# Power.net
KiCad netlist of a schematic drawn in Altium Designer
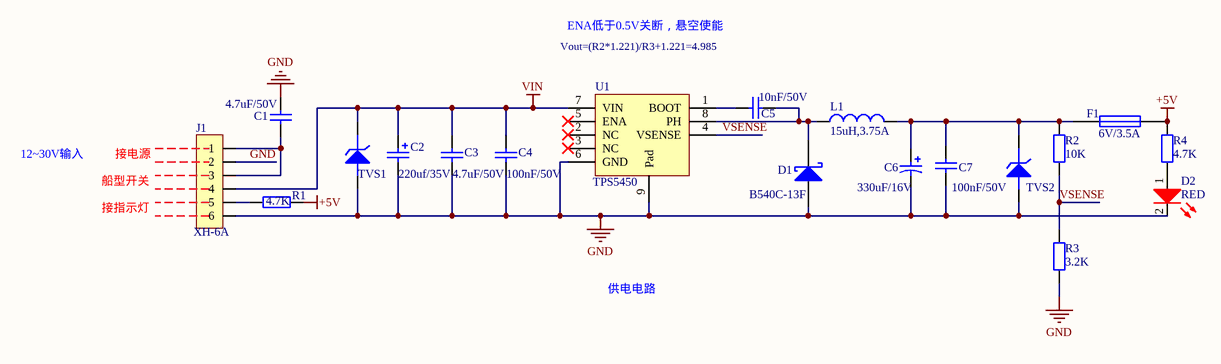
[diagram p0: Power.SchDoc]

(export (version "E")
  (design (tool "Eeschema 10.0.6"))
  (components
    (comp (ref "C1")
      (value "4.7uF/50V")
      (footprint "0603C")
      (description "瓷片电容,4.7uF,5%,X7R,50V,0603")
      (libsource (lib "SR SCH Library V02") (part "C4.7uF-0603"))
    )
    (comp (ref "C2")
      (value "220uf/35V")
      (footprint "CES-8x10R5mm")
      (description "铝电解电容,220uF,20%,35V,8*11.5")
      (libsource (lib "SR SCH Library V02") (part "C220uf/35V-8*11.5"))
    )
    (comp (ref "C3")
      (value "4.7uF/50V")
      (footprint "0603C")
      (description "瓷片电容,4.7uF,5%,X7R,50V,0603")
      (libsource (lib "SR SCH Library V02") (part "C4.7uF-0603"))
    )
    (comp (ref "C4")
      (value "100nF/50V")
      (footprint "0603C")
      (description "瓷片电容,100nF,5%,X7R,50V,0603")
      (libsource (lib "SR SCH Library V02") (part "C100nF/50V-0603"))
    )
    (comp (ref "C5")
      (value "10nF/50V")
      (footprint "0603C")
      (description "瓷片电容,10nF,5%,X7R,50V,0603")
      (libsource (lib "SR SCH Library V02") (part "C10nF/50V-0603"))
    )
    (comp (ref "C6")
      (value "330uF/16V")
      (footprint "CES-8 X11R7MM")
      (description "铝电解电容，330uF/16V，8*11.7")
      (libsource (lib "SR SCH Library V02") (part "C330uF/16V-8*11.7"))
    )
    (comp (ref "C7")
      (value "100nF/50V")
      (footprint "0603C")
      (description "瓷片电容,100nF,5%,X7R,50V,0603")
      (libsource (lib "SR SCH Library V02") (part "C100nF/50V-0603"))
    )
    (comp (ref "D1")
      (value "B540C-13F")
      (footprint "SMC")
      (description "肖特基二极管, 40V/5A, SMC（DO-214AB）封装")
      (libsource (lib "SR SCH Library V02") (part "B540C-13-F"))
    )
    (comp (ref "D2")
      (value "RED")
      (footprint "0603D")
      (description "LED，红光，0603")
      (libsource (lib "SR SCH Library V02") (part "LED-RED-0603"))
    )
    (comp (ref "F1")
      (value "6V/3.5A")
      (footprint "F1812")
      (description "保险丝,6V,3.5A,慢断,1812封装")
      (libsource (lib "SR SCH Library V02") (part "F-6V/3.5A"))
    )
    (comp (ref "J1")
      (value "XH-6A")
      (footprint "CN6-2.54")
      (description "CONN,XH-6A,6PIN,2.54mm插座")
      (libsource (lib "SR SCH Library V02") (part "CONN-XH-6A"))
    )
    (comp (ref "L1")
      (value "15uH,3.75A")
      (footprint "L12*12*6")
      (description "744771115，15uH，±20%，3.75A，外形尺寸：12x12x6mm")
      (libsource (lib "SR SCH Library V02") (part "L15uH-12*12*6"))
    )
    (comp (ref "R1")
      (value "4.7K")
      (footprint "0603R")
      (description "金属膜电阻,4.7K,1%,1/10W,0603")
      (libsource (lib "SR SCH Library V02") (part "R4.7K-0603"))
    )
    (comp (ref "R2")
      (value "10K")
      (footprint "0603R")
      (description "金属膜电阻,10K,0.1%,1/10W,0603")
      (libsource (lib "SR SCH Library V02") (part "R10K-0603-0.1%"))
    )
    (comp (ref "R3")
      (value "3.2K")
      (footprint "0603R")
      (description "金属膜电阻,3.2KK,0.1%,1/10W,0603")
      (libsource (lib "SR SCH Library V02") (part "R3.2K-0603-0.1%"))
    )
    (comp (ref "R4")
      (value "4.7K")
      (footprint "0603R")
      (description "金属膜电阻,4.7K,1%,1/10W,0603")
      (libsource (lib "") (part "R4.7K-0603_1"))
    )
    (comp (ref "TVS1")
      (value "1SMA26CAT3G")
      (footprint "DO-214AC")
      (description "TVS管，1SMA26CAT3G，DO214AC封装（SMA）")
      (libsource (lib "SR SCH Library V02") (part "1SMA26CAT3G"))
    )
    (comp (ref "TVS2")
      (value "1SMA6.0AT3D")
      (footprint "DO-214AC")
      (description "TVS管，1SMA6.0AT3D，DO214AC封装（SMA）")
      (libsource (lib "SR SCH Library V02") (part "1SMA6.0AT3D"))
    )
    (comp (ref "U1")
      (value "TPS5450")
      (footprint "SOIC8-P")
      (description "线性稳压器，SOIC-8封装，")
      (libsource (lib "SR SCH Library V02") (part "TPS5450"))
    )
  )
  (nets
    (net (code "1") (name "+5V") (class "Default")
      (node (ref "F1") (pin "2") (pinfunction "2_2") (pintype "passive"))
      (node (ref "R1") (pin "1") (pinfunction "1_1") (pintype "passive"))
      (node (ref "R4") (pin "2") (pinfunction "2_2") (pintype "passive"))
    )
    (net (code "2") (name "/VSENSE") (class "Default")
      (node (ref "R2") (pin "2") (pinfunction "2_2") (pintype "passive"))
      (node (ref "R3") (pin "2") (pinfunction "2_2") (pintype "passive"))
      (node (ref "U1") (pin "4") (pinfunction "VSENSE_4") (pintype "passive"))
    )
    (net (code "3") (name "GND") (class "Default")
      (node (ref "C1") (pin "2") (pinfunction "2_2") (pintype "passive"))
      (node (ref "C2") (pin "2") (pinfunction "2_2") (pintype "passive"))
      (node (ref "C3") (pin "1") (pinfunction "1_1") (pintype "passive"))
      (node (ref "C4") (pin "1") (pinfunction "1_1") (pintype "passive"))
      (node (ref "C6") (pin "2") (pinfunction "2_2") (pintype "passive"))
      (node (ref "C7") (pin "1") (pinfunction "1_1") (pintype "passive"))
      (node (ref "D1") (pin "1") (pinfunction "1_1") (pintype "passive"))
      (node (ref "D2") (pin "2") (pinfunction "2_2") (pintype "passive"))
      (node (ref "J1") (pin "2") (pinfunction "2_2") (pintype "passive"))
      (node (ref "J1") (pin "6") (pinfunction "6_6") (pintype "passive"))
      (node (ref "R3") (pin "1") (pinfunction "1_1") (pintype "passive"))
      (node (ref "TVS1") (pin "1") (pinfunction "1_1") (pintype "passive"))
      (node (ref "TVS2") (pin "1") (pinfunction "1_1") (pintype "passive"))
      (node (ref "U1") (pin "6") (pinfunction "GND_6") (pintype "passive"))
      (node (ref "U1") (pin "9") (pinfunction "Pad_9") (pintype "passive"))
    )
    (net (code "4") (name "Net-(C1-Pad1)") (class "Default")
      (node (ref "C1") (pin "1") (pinfunction "1_1") (pintype "passive"))
      (node (ref "J1") (pin "1") (pinfunction "1_1") (pintype "passive"))
      (node (ref "J1") (pin "3") (pinfunction "3_3") (pintype "passive"))
    )
    (net (code "5") (name "Net-(C6-Pad1)") (class "Default")
      (node (ref "C6") (pin "1") (pinfunction "1_1") (pintype "passive"))
      (node (ref "C7") (pin "2") (pinfunction "2_2") (pintype "passive"))
      (node (ref "F1") (pin "1") (pinfunction "1_1") (pintype "passive"))
      (node (ref "L1") (pin "2") (pinfunction "2_2") (pintype "passive"))
      (node (ref "R2") (pin "1") (pinfunction "1_1") (pintype "passive"))
      (node (ref "TVS2") (pin "2") (pinfunction "2_2") (pintype "passive"))
    )
    (net (code "6") (name "Net-(D2-Pad1)") (class "Default")
      (node (ref "D2") (pin "1") (pinfunction "1_1") (pintype "passive"))
      (node (ref "R4") (pin "1") (pinfunction "1_1") (pintype "passive"))
    )
    (net (code "7") (name "Net-(J1-Pad5)") (class "Default")
      (node (ref "J1") (pin "5") (pinfunction "5_5") (pintype "passive"))
      (node (ref "R1") (pin "2") (pinfunction "2_2") (pintype "passive"))
    )
    (net (code "8") (name "Net-(U1-BOOT)") (class "Default")
      (node (ref "C5") (pin "1") (pinfunction "1_1") (pintype "passive"))
      (node (ref "U1") (pin "1") (pinfunction "BOOT_1") (pintype "passive"))
    )
    (net (code "9") (name "Net-(U1-PH)") (class "Default")
      (node (ref "C5") (pin "2") (pinfunction "2_2") (pintype "passive"))
      (node (ref "D1") (pin "2") (pinfunction "2_2") (pintype "passive"))
      (node (ref "L1") (pin "1") (pinfunction "1_1") (pintype "passive"))
      (node (ref "U1") (pin "8") (pinfunction "PH_8") (pintype "passive"))
    )
    (net (code "10") (name "VIN") (class "Default")
      (node (ref "C2") (pin "1") (pinfunction "1_1") (pintype "passive"))
      (node (ref "C3") (pin "2") (pinfunction "2_2") (pintype "passive"))
      (node (ref "C4") (pin "2") (pinfunction "2_2") (pintype "passive"))
      (node (ref "J1") (pin "4") (pinfunction "4_4") (pintype "passive"))
      (node (ref "TVS1") (pin "2") (pinfunction "2_2") (pintype "passive"))
      (node (ref "U1") (pin "7") (pinfunction "VIN_7") (pintype "passive"))
    )
    (net (code "11") (name "unconnected-(U1-ENA-Pad5)") (class "Default")
      (node (ref "U1") (pin "5") (pinfunction "ENA_5") (pintype "passive+no_connect"))
    )
    (net (code "12") (name "unconnected-(U1-NC-Pad2)") (class "Default")
      (node (ref "U1") (pin "2") (pinfunction "NC_2") (pintype "passive+no_connect"))
    )
    (net (code "13") (name "unconnected-(U1-NC-Pad3)") (class "Default")
      (node (ref "U1") (pin "3") (pinfunction "NC_3") (pintype "passive+no_connect"))
    )
  )
)
